# AC_filament_driver.net
KiCad netlist of a schematic drawn in EAGLE
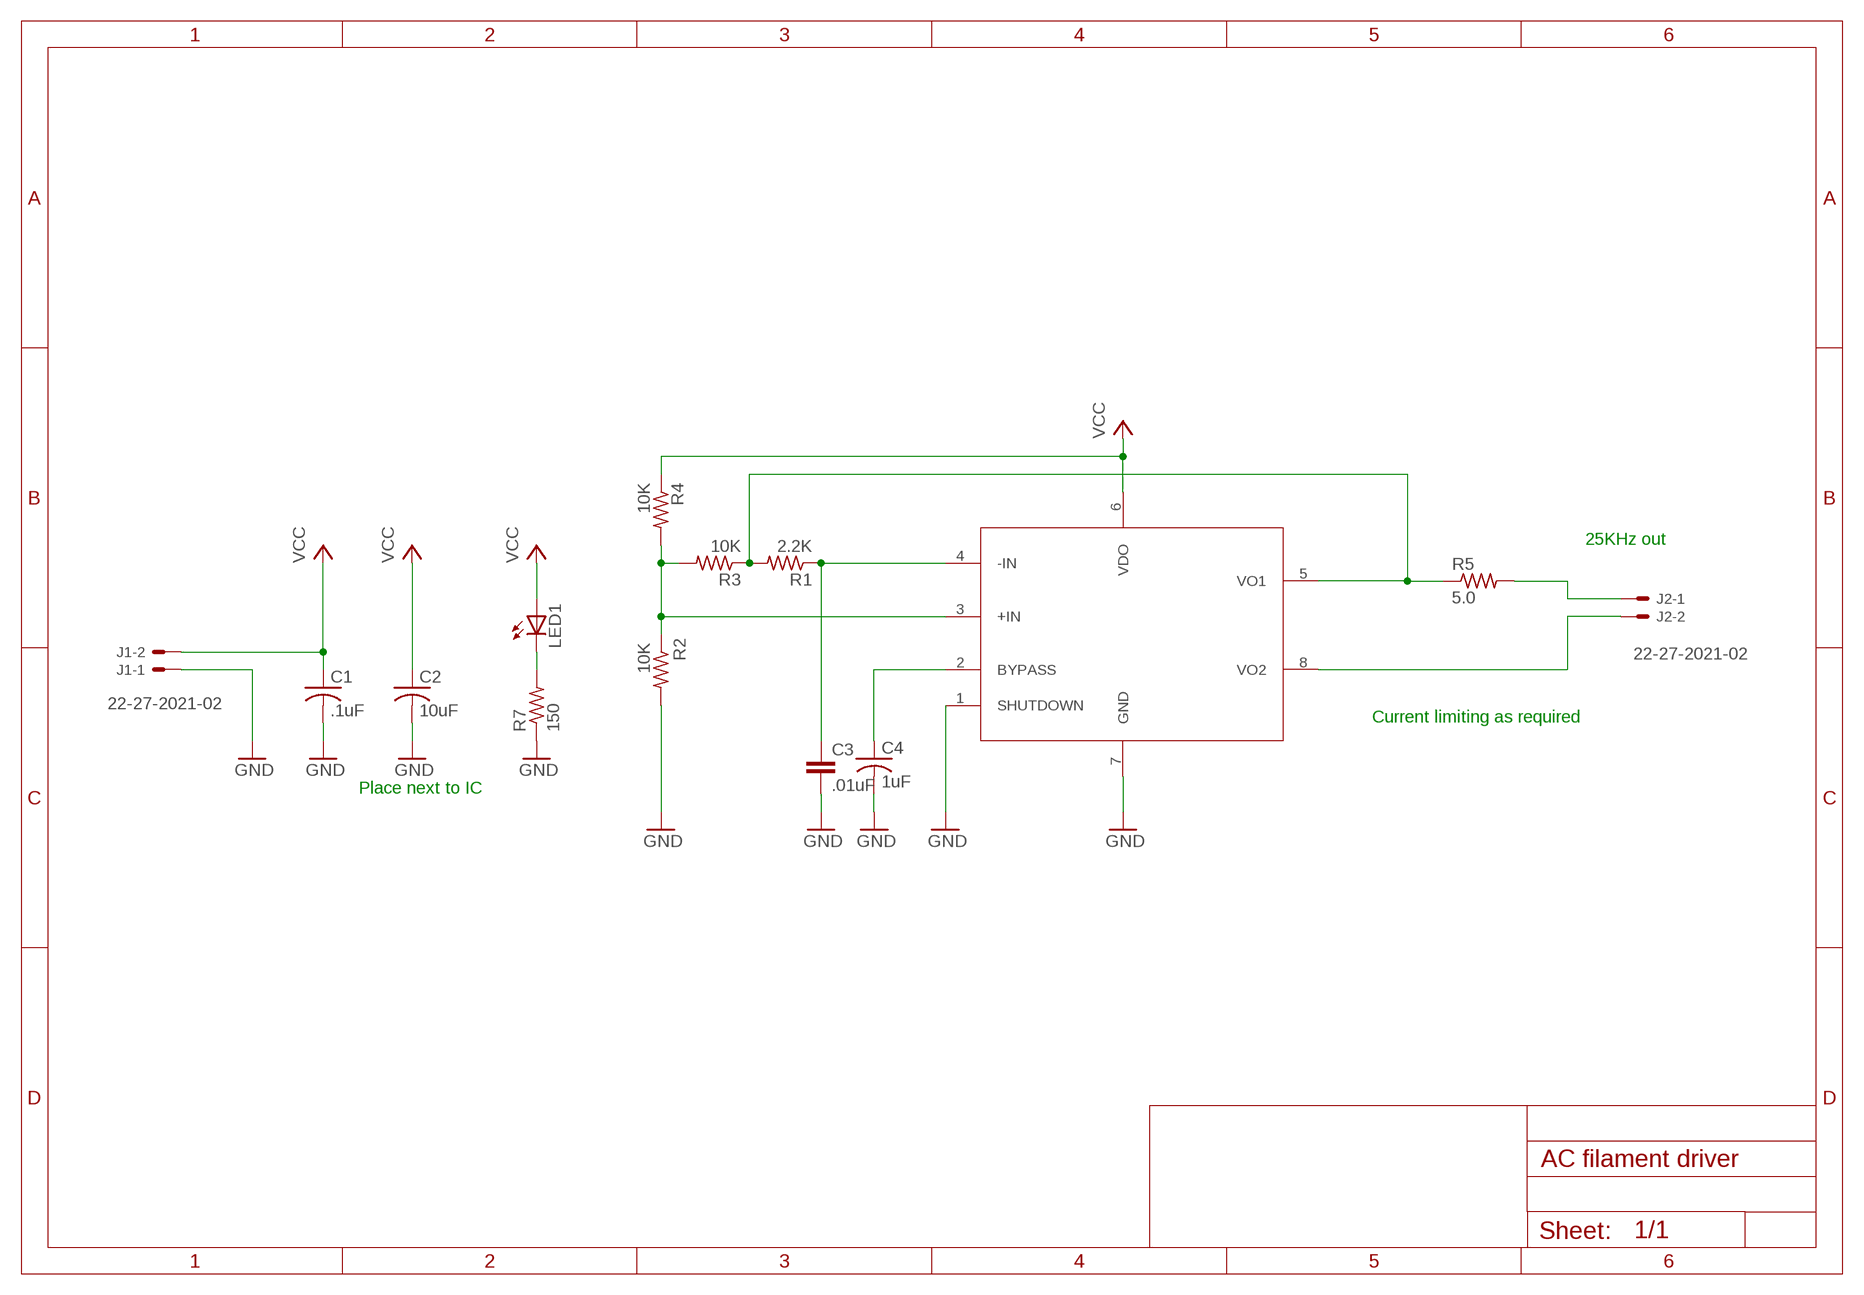
[diagram p0: schematic, sheet 1]

(export (version "E")
  (design (tool "Eeschema 10.0.6"))
  (components
    (comp (ref "C1")
      (value ".1uF")
      (footprint "eagle-import:C050-024X044")
      (libsource (lib "eagle-import") (part "rcl_334_C-US050-024X044"))
    )
    (comp (ref "C2")
      (value "10uF")
      (footprint "eagle-import:C025-060X050")
      (libsource (lib "eagle-import") (part "C-US025-060X050"))
    )
    (comp (ref "C3")
      (value ".01uF")
      (footprint "eagle-import:C0805")
      (libsource (lib "eagle-import") (part "C-EUC0805"))
    )
    (comp (ref "C4")
      (value "1uF")
      (footprint "eagle-import:C025-060X050")
      (libsource (lib "eagle-import") (part "C-US025-060X050"))
    )
    (comp (ref "J1")
      (value "22-27-2021-02")
      (footprint "eagle-import:6410-02")
      (fields (field (name "MF") "MOLEX"))
      (libsource (lib "eagle-import") (part "22-?-0227-2021"))
    )
    (comp (ref "J2")
      (value "22-27-2021-02")
      (footprint "eagle-import:6410-02")
      (fields (field (name "MF") "MOLEX"))
      (libsource (lib "eagle-import") (part "22-?-0227-2021"))
    )
    (comp (ref "LED1")
      (value "LEDCHIP-LED0805")
      (footprint "eagle-import:CHIP-LED0805")
      (libsource (lib "eagle-import") (part "LEDCHIP-LED0805"))
    )
    (comp (ref "R1")
      (value "2.2K")
      (footprint "eagle-import:R0805")
      (libsource (lib "eagle-import") (part "R-US_R0805"))
    )
    (comp (ref "R2")
      (value "10K")
      (footprint "eagle-import:R0805")
      (libsource (lib "eagle-import") (part "R-US_R0805"))
    )
    (comp (ref "R3")
      (value "10K")
      (footprint "eagle-import:R0805")
      (libsource (lib "eagle-import") (part "R-US_R0805"))
    )
    (comp (ref "R4")
      (value "10K")
      (footprint "eagle-import:R0805")
      (libsource (lib "eagle-import") (part "R-US_R0805"))
    )
    (comp (ref "R5")
      (value "5.0")
      (footprint "eagle-import:R0805")
      (libsource (lib "eagle-import") (part "rcl_334_R-US_R0805"))
    )
    (comp (ref "R7")
      (value "150")
      (footprint "eagle-import:R0805")
      (libsource (lib "eagle-import") (part "R-US_R0805"))
    )
    (comp (ref "U1")
      (value "LM9022")
      (footprint "eagle-import:SOIC127P600X175-8N")
      (libsource (lib "eagle-import") (part "LM9022"))
    )
  )
  (nets
    (net (code "1") (name "GND") (class "Default")
      (node (ref "C1") (pin "2") (pinfunction "2_2") (pintype "passive"))
      (node (ref "C2") (pin "2") (pinfunction "2_2") (pintype "passive"))
      (node (ref "C3") (pin "2") (pinfunction "2_2") (pintype "passive"))
      (node (ref "C4") (pin "2") (pinfunction "2_2") (pintype "passive"))
      (node (ref "J1") (pin "1") (pinfunction "S_1") (pintype "passive"))
      (node (ref "R2") (pin "2") (pinfunction "2_2") (pintype "passive"))
      (node (ref "R7") (pin "1") (pinfunction "1_1") (pintype "passive"))
      (node (ref "U1") (pin "1") (pinfunction "SHUTDOWN_1") (pintype "input"))
      (node (ref "U1") (pin "7") (pinfunction "GND_7") (pintype "power_in"))
    )
    (net (code "2") (name "Net-(J2A-S)") (class "Default")
      (node (ref "J2") (pin "1") (pinfunction "S_1") (pintype "passive"))
      (node (ref "R5") (pin "2") (pinfunction "2_2") (pintype "passive"))
    )
    (net (code "3") (name "Net-(J2B-S)") (class "Default")
      (node (ref "J2") (pin "2") (pinfunction "S_2") (pintype "passive"))
      (node (ref "U1") (pin "8") (pinfunction "VO2_8") (pintype "output"))
    )
    (net (code "4") (name "Net-(LED1-PadC)") (class "Default")
      (node (ref "LED1") (pin "C") (pinfunction "C_C") (pintype "passive"))
      (node (ref "R7") (pin "2") (pinfunction "2_2") (pintype "passive"))
    )
    (net (code "5") (name "Net-(U1-+IN)") (class "Default")
      (node (ref "R2") (pin "1") (pinfunction "1_1") (pintype "passive"))
      (node (ref "R3") (pin "2") (pinfunction "2_2") (pintype "passive"))
      (node (ref "R4") (pin "2") (pinfunction "2_2") (pintype "passive"))
      (node (ref "U1") (pin "3") (pinfunction "+IN_3") (pintype "input"))
    )
    (net (code "6") (name "Net-(U1--IN)") (class "Default")
      (node (ref "C3") (pin "1") (pinfunction "1_1") (pintype "passive"))
      (node (ref "R1") (pin "1") (pinfunction "1_1") (pintype "passive"))
      (node (ref "U1") (pin "4") (pinfunction "-IN_4") (pintype "input"))
    )
    (net (code "7") (name "Net-(U1-BYPASS)") (class "Default")
      (node (ref "C4") (pin "1") (pinfunction "1_1") (pintype "passive"))
      (node (ref "U1") (pin "2") (pinfunction "BYPASS_2") (pintype "input"))
    )
    (net (code "8") (name "Net-(U1-VO1)") (class "Default")
      (node (ref "R1") (pin "2") (pinfunction "2_2") (pintype "passive"))
      (node (ref "R3") (pin "1") (pinfunction "1_1") (pintype "passive"))
      (node (ref "R5") (pin "1") (pinfunction "1_1") (pintype "passive"))
      (node (ref "U1") (pin "5") (pinfunction "VO1_5") (pintype "output"))
    )
    (net (code "9") (name "VCC") (class "Default")
      (node (ref "C1") (pin "1") (pinfunction "1_1") (pintype "passive"))
      (node (ref "C2") (pin "1") (pinfunction "1_1") (pintype "passive"))
      (node (ref "J1") (pin "2") (pinfunction "S_2") (pintype "passive"))
      (node (ref "LED1") (pin "A") (pinfunction "A_A") (pintype "passive"))
      (node (ref "R4") (pin "1") (pinfunction "1_1") (pintype "passive"))
      (node (ref "U1") (pin "6") (pinfunction "VDO_6") (pintype "power_in"))
    )
  )
)
